# Bluetooth_Module_V1.net
KiCad netlist of a schematic drawn in Altium Designer
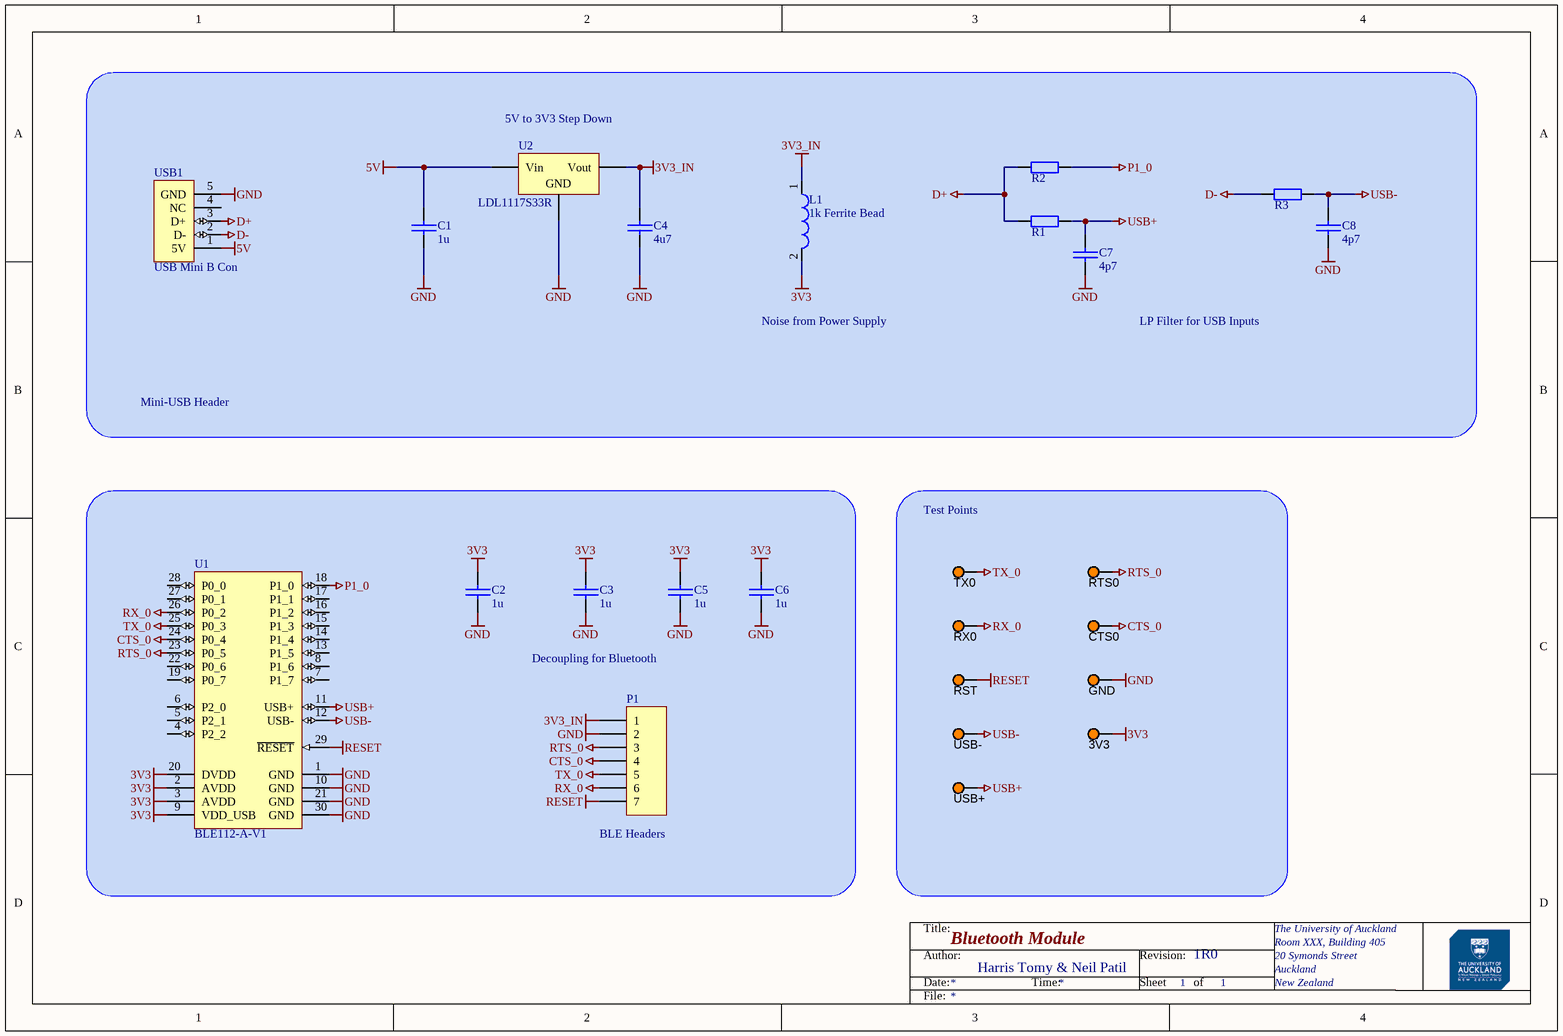
[diagram p0: Bluetooth_Module_V1.SchDoc]

(export (version "E")
  (design (tool "Eeschema 10.0.6"))
  (components
    (comp (ref "3V3")
      (value "5003")
      (footprint "TP_TH")
      (description "Test Point, Orange, 1-Pin THD, RoHS")
      (libsource (lib "EE209_Library") (part "TestPoint"))
    )
    (comp (ref "C1")
      (value "1u")
      (footprint "C0805")
      (description "CCAP0805")
      (fields (field (name "MPN") "?"))
      (libsource (lib "E209_Lib") (part "CCAP0805"))
    )
    (comp (ref "C2")
      (value "1u")
      (footprint "C0805")
      (description "CCAP0805")
      (fields (field (name "MPN") "?"))
      (libsource (lib "E209_Lib") (part "CCAP0805"))
    )
    (comp (ref "C3")
      (value "1u")
      (footprint "C0805")
      (description "CCAP0805")
      (fields (field (name "MPN") "?"))
      (libsource (lib "E209_Lib") (part "CCAP0805"))
    )
    (comp (ref "C4")
      (value "4u7")
      (footprint "C1206")
      (description "CAP CER 0.1UF 100V C0G 1206")
      (fields (field (name "MPN") "C3216C0G2A104J160AC") (field (name "MANUFACTURER") "TDK Corporation"))
      (libsource (lib "E209_Lib") (part "Cap CER Decoup C3216C0G2A104J160AC"))
    )
    (comp (ref "C5")
      (value "1u")
      (footprint "C0805")
      (description "CCAP0805")
      (fields (field (name "MPN") "?"))
      (libsource (lib "E209_Lib") (part "CCAP0805"))
    )
    (comp (ref "C6")
      (value "1u")
      (footprint "C0805")
      (description "CCAP0805")
      (fields (field (name "MPN") "?"))
      (libsource (lib "E209_Lib") (part "CCAP0805"))
    )
    (comp (ref "C7")
      (value "4p7")
      (footprint "C0805")
      (description "CCAP0805")
      (fields (field (name "MPN") "?"))
      (libsource (lib "E209_Lib") (part "CCAP0805"))
    )
    (comp (ref "C8")
      (value "4p7")
      (footprint "C0805")
      (description "CCAP0805")
      (fields (field (name "MPN") "?"))
      (libsource (lib "E209_Lib") (part "CCAP0805"))
    )
    (comp (ref "CTS0")
      (value "5003")
      (footprint "TP_TH")
      (description "Test Point, Orange, 1-Pin THD, RoHS")
      (libsource (lib "EE209_Library") (part "TestPoint"))
    )
    (comp (ref "GND")
      (value "5003")
      (footprint "TP_TH")
      (description "Test Point, Orange, 1-Pin THD, RoHS")
      (libsource (lib "EE209_Library") (part "TestPoint"))
    )
    (comp (ref "L1")
      (value "1k Ferrite Bead")
      (footprint "SMD-1206")
      (description "SMD EMI Suppression Ferrite Bead WE-CBF, Z = 120 Ohm")
      (fields (field (name "PARTNUMBER") "742792113"))
      (libsource (lib "FE_Bead_1206") (part "742792113"))
    )
    (comp (ref "P1")
      (value "BLE Headers")
      (footprint "HDR1X7")
      (description "Header, 7-Pin")
      (fields (field (name "PUBLISHER") "Altium Limited"))
      (libsource (lib "Miscellaneous Connectors") (part "Header 7"))
    )
    (comp (ref "R1")
      (value "Resistor 0805")
      (footprint "R0805")
      (description "RES0805")
      (fields (field (name "MPN") "?"))
      (libsource (lib "E209_Lib") (part "RES0805"))
    )
    (comp (ref "R2")
      (value "Resistor 0805")
      (footprint "R0805")
      (description "RES0805")
      (fields (field (name "MPN") "?"))
      (libsource (lib "") (part "RES0805_1"))
    )
    (comp (ref "R3")
      (value "Resistor 0805")
      (footprint "R0805")
      (description "RES0805")
      (fields (field (name "MPN") "?"))
      (libsource (lib "E209_Lib") (part "RES0805"))
    )
    (comp (ref "RST")
      (value "5003")
      (footprint "TP_TH")
      (description "Test Point, Orange, 1-Pin THD, RoHS")
      (libsource (lib "EE209_Library") (part "TestPoint"))
    )
    (comp (ref "RTS0")
      (value "5003")
      (footprint "TP_TH")
      (description "Test Point, Orange, 1-Pin THD, RoHS")
      (libsource (lib "EE209_Library") (part "TestPoint"))
    )
    (comp (ref "RX0")
      (value "5003")
      (footprint "TP_TH")
      (description "Test Point, Orange, 1-Pin THD, RoHS")
      (libsource (lib "EE209_Library") (part "TestPoint"))
    )
    (comp (ref "TX0")
      (value "5003")
      (footprint "TP_TH")
      (description "Test Point, Orange, 1-Pin THD, RoHS")
      (libsource (lib "EE209_Library") (part "TestPoint"))
    )
    (comp (ref "U1")
      (value "BLE112-A-V1")
      (footprint "BLUE-BLE112-A-V1_V")
      (libsource (lib "BLE112") (part "BLE112-A-V1"))
    )
    (comp (ref "U2")
      (value "LDL1117S33R")
      (footprint "SOT223L")
      (description "IC REG LINEAR 3.3V 1.2A SOT223")
      (fields (field (name "MANUFACTURER") "STMicroelectronics"))
      (libsource (lib "E209_Lib") (part "LDO LDL1117S33R"))
    )
    (comp (ref "USB+")
      (value "5003")
      (footprint "TP_TH")
      (description "Test Point, Orange, 1-Pin THD, RoHS")
      (libsource (lib "EE209_Library") (part "TestPoint"))
    )
    (comp (ref "USB-")
      (value "5003")
      (footprint "TP_TH")
      (description "Test Point, Orange, 1-Pin THD, RoHS")
      (libsource (lib "EE209_Library") (part "TestPoint"))
    )
    (comp (ref "USB1")
      (value "USB Mini B Con")
      (footprint "USB_UJ2MAB")
      (libsource (lib "CommonDevices_V1") (part "USBMiniB"))
    )
  )
  (nets
    (net (code "1") (name "3V3") (class "Default")
      (node (ref "3V3") (pin "1") (pinfunction "1_1") (pintype "passive"))
      (node (ref "C2") (pin "2") (pinfunction "2_2") (pintype "passive"))
      (node (ref "C3") (pin "2") (pinfunction "2_2") (pintype "passive"))
      (node (ref "C5") (pin "2") (pinfunction "2_2") (pintype "passive"))
      (node (ref "C6") (pin "2") (pinfunction "2_2") (pintype "passive"))
      (node (ref "L1") (pin "2") (pinfunction "2_2") (pintype "passive"))
      (node (ref "U1") (pin "2") (pinfunction "AVDD_2") (pintype "power_in"))
      (node (ref "U1") (pin "20") (pinfunction "DVDD_20") (pintype "power_in"))
      (node (ref "U1") (pin "3") (pinfunction "AVDD_3") (pintype "power_in"))
      (node (ref "U1") (pin "9") (pinfunction "VDD_USB_9") (pintype "power_in"))
    )
    (net (code "2") (name "3V3_IN") (class "Default")
      (node (ref "C4") (pin "2") (pinfunction "2_2") (pintype "passive"))
      (node (ref "L1") (pin "1") (pinfunction "1_1") (pintype "passive"))
      (node (ref "P1") (pin "1") (pinfunction "1_1") (pintype "passive"))
      (node (ref "U2") (pin "2") (pinfunction "Vout_2") (pintype "passive"))
    )
    (net (code "3") (name "5V") (class "Default")
      (node (ref "C1") (pin "2") (pinfunction "2_2") (pintype "passive"))
      (node (ref "U2") (pin "3") (pinfunction "Vin_3") (pintype "passive"))
      (node (ref "USB1") (pin "1") (pinfunction "5V_1") (pintype "passive"))
    )
    (net (code "4") (name "CTS_0") (class "Default")
      (node (ref "CTS0") (pin "1") (pinfunction "1_1") (pintype "passive"))
      (node (ref "P1") (pin "4") (pinfunction "4_4") (pintype "passive"))
      (node (ref "U1") (pin "24") (pinfunction "P0_4_24") (pintype "bidirectional"))
    )
    (net (code "5") (name "D+") (class "Default")
      (node (ref "R1") (pin "2") (pinfunction "2_2") (pintype "passive"))
      (node (ref "R2") (pin "1") (pinfunction "1_1") (pintype "passive"))
      (node (ref "USB1") (pin "3") (pinfunction "D+_3") (pintype "bidirectional"))
    )
    (net (code "6") (name "D-") (class "Default")
      (node (ref "R3") (pin "2") (pinfunction "2_2") (pintype "passive"))
      (node (ref "USB1") (pin "2") (pinfunction "D-_2") (pintype "bidirectional"))
    )
    (net (code "7") (name "GND") (class "Default")
      (node (ref "C1") (pin "1") (pinfunction "1_1") (pintype "passive"))
      (node (ref "C2") (pin "1") (pinfunction "1_1") (pintype "passive"))
      (node (ref "C3") (pin "1") (pinfunction "1_1") (pintype "passive"))
      (node (ref "C4") (pin "1") (pinfunction "1_1") (pintype "passive"))
      (node (ref "C5") (pin "1") (pinfunction "1_1") (pintype "passive"))
      (node (ref "C6") (pin "1") (pinfunction "1_1") (pintype "passive"))
      (node (ref "C7") (pin "1") (pinfunction "1_1") (pintype "passive"))
      (node (ref "C8") (pin "1") (pinfunction "1_1") (pintype "passive"))
      (node (ref "GND") (pin "1") (pinfunction "1_1") (pintype "passive"))
      (node (ref "P1") (pin "2") (pinfunction "2_2") (pintype "passive"))
      (node (ref "U1") (pin "1") (pinfunction "GND_1") (pintype "power_in"))
      (node (ref "U1") (pin "10") (pinfunction "GND_10") (pintype "power_in"))
      (node (ref "U1") (pin "21") (pinfunction "GND_21") (pintype "power_in"))
      (node (ref "U1") (pin "30") (pinfunction "GND_30") (pintype "power_in"))
      (node (ref "U2") (pin "1") (pinfunction "GND_1") (pintype "passive"))
      (node (ref "USB1") (pin "5") (pinfunction "GND_5") (pintype "passive"))
    )
    (net (code "8") (name "P1_0") (class "Default")
      (node (ref "R2") (pin "2") (pinfunction "2_2") (pintype "passive"))
      (node (ref "U1") (pin "18") (pinfunction "P1_0_18") (pintype "bidirectional"))
    )
    (net (code "9") (name "RESET") (class "Default")
      (node (ref "P1") (pin "7") (pinfunction "7_7") (pintype "passive"))
      (node (ref "RST") (pin "1") (pinfunction "1_1") (pintype "passive"))
      (node (ref "U1") (pin "29") (pinfunction "~{RESET}_29") (pintype "input"))
    )
    (net (code "10") (name "RTS_0") (class "Default")
      (node (ref "P1") (pin "3") (pinfunction "3_3") (pintype "passive"))
      (node (ref "RTS0") (pin "1") (pinfunction "1_1") (pintype "passive"))
      (node (ref "U1") (pin "23") (pinfunction "P0_5_23") (pintype "bidirectional"))
    )
    (net (code "11") (name "RX_0") (class "Default")
      (node (ref "P1") (pin "6") (pinfunction "6_6") (pintype "passive"))
      (node (ref "RX0") (pin "1") (pinfunction "1_1") (pintype "passive"))
      (node (ref "U1") (pin "26") (pinfunction "P0_2_26") (pintype "bidirectional"))
    )
    (net (code "12") (name "TX_0") (class "Default")
      (node (ref "P1") (pin "5") (pinfunction "5_5") (pintype "passive"))
      (node (ref "TX0") (pin "1") (pinfunction "1_1") (pintype "passive"))
      (node (ref "U1") (pin "25") (pinfunction "P0_3_25") (pintype "bidirectional"))
    )
    (net (code "13") (name "USB+") (class "Default")
      (node (ref "C7") (pin "2") (pinfunction "2_2") (pintype "passive"))
      (node (ref "R1") (pin "1") (pinfunction "1_1") (pintype "passive"))
      (node (ref "U1") (pin "11") (pinfunction "USB+_11") (pintype "bidirectional"))
      (node (ref "USB+") (pin "1") (pinfunction "1_1") (pintype "passive"))
    )
    (net (code "14") (name "USB-") (class "Default")
      (node (ref "C8") (pin "2") (pinfunction "2_2") (pintype "passive"))
      (node (ref "R3") (pin "1") (pinfunction "1_1") (pintype "passive"))
      (node (ref "U1") (pin "12") (pinfunction "USB-_12") (pintype "bidirectional"))
      (node (ref "USB-") (pin "1") (pinfunction "1_1") (pintype "passive"))
    )
    (net (code "15") (name "unconnected-(U1-P0_0-Pad28)") (class "Default")
      (node (ref "U1") (pin "28") (pinfunction "P0_0_28") (pintype "bidirectional"))
    )
    (net (code "16") (name "unconnected-(U1-P0_1-Pad27)") (class "Default")
      (node (ref "U1") (pin "27") (pinfunction "P0_1_27") (pintype "bidirectional"))
    )
    (net (code "17") (name "unconnected-(U1-P0_6-Pad22)") (class "Default")
      (node (ref "U1") (pin "22") (pinfunction "P0_6_22") (pintype "bidirectional"))
    )
    (net (code "18") (name "unconnected-(U1-P0_7-Pad19)") (class "Default")
      (node (ref "U1") (pin "19") (pinfunction "P0_7_19") (pintype "bidirectional"))
    )
    (net (code "19") (name "unconnected-(U1-P1_1-Pad17)") (class "Default")
      (node (ref "U1") (pin "17") (pinfunction "P1_1_17") (pintype "bidirectional"))
    )
    (net (code "20") (name "unconnected-(U1-P1_2-Pad16)") (class "Default")
      (node (ref "U1") (pin "16") (pinfunction "P1_2_16") (pintype "bidirectional"))
    )
    (net (code "21") (name "unconnected-(U1-P1_3-Pad15)") (class "Default")
      (node (ref "U1") (pin "15") (pinfunction "P1_3_15") (pintype "bidirectional"))
    )
    (net (code "22") (name "unconnected-(U1-P1_4-Pad14)") (class "Default")
      (node (ref "U1") (pin "14") (pinfunction "P1_4_14") (pintype "bidirectional"))
    )
    (net (code "23") (name "unconnected-(U1-P1_5-Pad13)") (class "Default")
      (node (ref "U1") (pin "13") (pinfunction "P1_5_13") (pintype "bidirectional"))
    )
    (net (code "24") (name "unconnected-(U1-P1_6-Pad8)") (class "Default")
      (node (ref "U1") (pin "8") (pinfunction "P1_6_8") (pintype "bidirectional"))
    )
    (net (code "25") (name "unconnected-(U1-P1_7-Pad7)") (class "Default")
      (node (ref "U1") (pin "7") (pinfunction "P1_7_7") (pintype "bidirectional"))
    )
    (net (code "26") (name "unconnected-(U1-P2_0-Pad6)") (class "Default")
      (node (ref "U1") (pin "6") (pinfunction "P2_0_6") (pintype "bidirectional"))
    )
    (net (code "27") (name "unconnected-(U1-P2_1-Pad5)") (class "Default")
      (node (ref "U1") (pin "5") (pinfunction "P2_1_5") (pintype "bidirectional"))
    )
    (net (code "28") (name "unconnected-(U1-P2_2-Pad4)") (class "Default")
      (node (ref "U1") (pin "4") (pinfunction "P2_2_4") (pintype "bidirectional"))
    )
    (net (code "29") (name "unconnected-(USB1-NC-Pad4)") (class "Default")
      (node (ref "USB1") (pin "4") (pinfunction "NC_4") (pintype "passive"))
    )
  )
)
